# TransmitAnalog.net
KiCad netlist of a schematic drawn in EAGLE
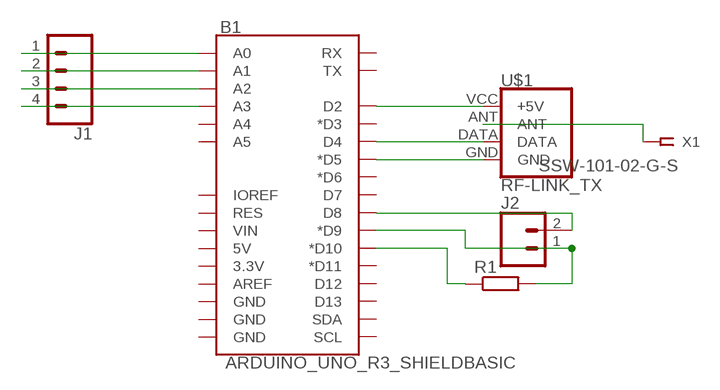
[diagram p0: schematic, sheet 1]

(export (version "E")
  (design (tool "Eeschema 10.0.6"))
  (components
    (comp (ref "B1")
      (value "ARDUINO_UNO_R3_SHIELDBASIC")
      (footprint "eagle-import:UNO_R3_SHIELD")
      (libsource (lib "eagle-import") (part "ARDUINO_UNO_R3_SHIELDBASIC"))
    )
    (comp (ref "J1")
      (value "CONN_04")
      (footprint "eagle-import:1X04")
      (libsource (lib "eagle-import") (part "CONN_04"))
    )
    (comp (ref "J2")
      (value "CONN_02")
      (footprint "eagle-import:1X02")
      (libsource (lib "eagle-import") (part "CONN_02"))
    )
    (comp (ref "R1")
      (value "R-EU_0204/7")
      (footprint "eagle-import:0204_7")
      (libsource (lib "eagle-import") (part "R-EU_0204/7"))
    )
    (comp (ref "U$1")
      (value "RF-LINK_TX")
      (footprint "eagle-import:RF-LINK_TX")
      (libsource (lib "eagle-import") (part "RF-LINK_TX"))
    )
    (comp (ref "X1")
      (value "SSW-101-02-G-S")
      (footprint "eagle-import:SSW-101-02-G-S")
      (fields (field (name "MF") "Samtec Inc."))
      (libsource (lib "eagle-import") (part "SSW-101-02-G-S"))
    )
  )
  (nets
    (net (code "1") (name "Net-(B1-*D5)") (class "Default")
      (node (ref "B1") (pin "D5") (pinfunction "*D5_D5") (pintype "bidirectional"))
      (node (ref "U$1") (pin "GND") (pinfunction "GND_GND") (pintype "power_in"))
    )
    (net (code "2") (name "Net-(B1-*D9)") (class "Default")
      (node (ref "B1") (pin "D9") (pinfunction "*D9_D9") (pintype "bidirectional"))
      (node (ref "J2") (pin "1") (pinfunction "1_1") (pintype "passive"))
      (node (ref "R1") (pin "2") (pinfunction "2_2") (pintype "passive"))
    )
    (net (code "3") (name "Net-(B1-*D10)") (class "Default")
      (node (ref "B1") (pin "D10") (pinfunction "*D10_D10") (pintype "bidirectional"))
      (node (ref "R1") (pin "1") (pinfunction "1_1") (pintype "passive"))
    )
    (net (code "4") (name "Net-(B1-PadA0)") (class "Default")
      (node (ref "B1") (pin "A0") (pinfunction "A0_A0") (pintype "bidirectional"))
      (node (ref "J1") (pin "1") (pinfunction "1_1") (pintype "passive"))
    )
    (net (code "5") (name "Net-(B1-PadA1)") (class "Default")
      (node (ref "B1") (pin "A1") (pinfunction "A1_A1") (pintype "bidirectional"))
      (node (ref "J1") (pin "2") (pinfunction "2_2") (pintype "passive"))
    )
    (net (code "6") (name "Net-(B1-PadA2)") (class "Default")
      (node (ref "B1") (pin "A2") (pinfunction "A2_A2") (pintype "bidirectional"))
      (node (ref "J1") (pin "3") (pinfunction "3_3") (pintype "passive"))
    )
    (net (code "7") (name "Net-(B1-PadA3)") (class "Default")
      (node (ref "B1") (pin "A3") (pinfunction "A3_A3") (pintype "bidirectional"))
      (node (ref "J1") (pin "4") (pinfunction "4_4") (pintype "passive"))
    )
    (net (code "8") (name "Net-(B1-PadD4)") (class "Default")
      (node (ref "B1") (pin "D4") (pinfunction "D4_D4") (pintype "bidirectional"))
      (node (ref "U$1") (pin "DATA") (pinfunction "DATA_DATA") (pintype "input"))
    )
    (net (code "9") (name "Net-(B1-PadD8)") (class "Default")
      (node (ref "B1") (pin "D8") (pinfunction "D8_D8") (pintype "bidirectional"))
      (node (ref "J2") (pin "2") (pinfunction "2_2") (pintype "passive"))
    )
    (net (code "10") (name "Net-(U$1-+5V)") (class "Default")
      (node (ref "B1") (pin "D2") (pinfunction "D2_D2") (pintype "bidirectional"))
      (node (ref "U$1") (pin "VCC") (pinfunction "+5V_VCC") (pintype "power_in"))
    )
    (net (code "11") (name "Net-(U$1-PadANT)") (class "Default")
      (node (ref "U$1") (pin "ANT") (pinfunction "ANT_ANT") (pintype "passive"))
      (node (ref "X1") (pin "1") (pinfunction "1_1") (pintype "passive"))
    )
    (net (code "12") (name "unconnected-(B1-*D3-PadD3)") (class "Default")
      (node (ref "B1") (pin "D3") (pinfunction "*D3_D3") (pintype "bidirectional"))
    )
    (net (code "13") (name "unconnected-(B1-*D6-PadD6)") (class "Default")
      (node (ref "B1") (pin "D6") (pinfunction "*D6_D6") (pintype "bidirectional"))
    )
    (net (code "14") (name "unconnected-(B1-*D11-PadD11)") (class "Default")
      (node (ref "B1") (pin "D11") (pinfunction "*D11_D11") (pintype "bidirectional"))
    )
    (net (code "15") (name "unconnected-(B1-GND-PadGND@0)") (class "Default")
      (node (ref "B1") (pin "GND@0") (pinfunction "GND_GND@0") (pintype "bidirectional"))
    )
    (net (code "16") (name "unconnected-(B1-GND-PadGND@1)") (class "Default")
      (node (ref "B1") (pin "GND@1") (pinfunction "GND_GND@1") (pintype "bidirectional"))
    )
    (net (code "17") (name "unconnected-(B1-GND-PadGND@2)") (class "Default")
      (node (ref "B1") (pin "GND@2") (pinfunction "GND_GND@2") (pintype "bidirectional"))
    )
    (net (code "18") (name "unconnected-(B1-Pad3.3V)") (class "Default")
      (node (ref "B1") (pin "3.3V") (pinfunction "3.3V_3.3V") (pintype "bidirectional"))
    )
    (net (code "19") (name "unconnected-(B1-Pad5V)") (class "Default")
      (node (ref "B1") (pin "5V") (pinfunction "5V_5V") (pintype "bidirectional"))
    )
    (net (code "20") (name "unconnected-(B1-PadA4)") (class "Default")
      (node (ref "B1") (pin "A4") (pinfunction "A4_A4") (pintype "bidirectional"))
    )
    (net (code "21") (name "unconnected-(B1-PadA5)") (class "Default")
      (node (ref "B1") (pin "A5") (pinfunction "A5_A5") (pintype "bidirectional"))
    )
    (net (code "22") (name "unconnected-(B1-PadAREF)") (class "Default")
      (node (ref "B1") (pin "AREF") (pinfunction "AREF_AREF") (pintype "bidirectional"))
    )
    (net (code "23") (name "unconnected-(B1-PadD7)") (class "Default")
      (node (ref "B1") (pin "D7") (pinfunction "D7_D7") (pintype "bidirectional"))
    )
    (net (code "24") (name "unconnected-(B1-PadD12)") (class "Default")
      (node (ref "B1") (pin "D12") (pinfunction "D12_D12") (pintype "bidirectional"))
    )
    (net (code "25") (name "unconnected-(B1-PadD13)") (class "Default")
      (node (ref "B1") (pin "D13") (pinfunction "D13_D13") (pintype "bidirectional"))
    )
    (net (code "26") (name "unconnected-(B1-PadIOREF)") (class "Default")
      (node (ref "B1") (pin "IOREF") (pinfunction "IOREF_IOREF") (pintype "bidirectional"))
    )
    (net (code "27") (name "unconnected-(B1-PadRES)") (class "Default")
      (node (ref "B1") (pin "RES") (pinfunction "RES_RES") (pintype "bidirectional"))
    )
    (net (code "28") (name "unconnected-(B1-PadRX)") (class "Default")
      (node (ref "B1") (pin "RX") (pinfunction "RX_RX") (pintype "bidirectional"))
    )
    (net (code "29") (name "unconnected-(B1-PadSCL)") (class "Default")
      (node (ref "B1") (pin "SCL") (pinfunction "SCL_SCL") (pintype "bidirectional"))
    )
    (net (code "30") (name "unconnected-(B1-PadSDA)") (class "Default")
      (node (ref "B1") (pin "SDA") (pinfunction "SDA_SDA") (pintype "bidirectional"))
    )
    (net (code "31") (name "unconnected-(B1-PadTX)") (class "Default")
      (node (ref "B1") (pin "TX") (pinfunction "TX_TX") (pintype "bidirectional"))
    )
    (net (code "32") (name "unconnected-(B1-PadVIN)") (class "Default")
      (node (ref "B1") (pin "VIN") (pinfunction "VIN_VIN") (pintype "bidirectional"))
    )
  )
)
